# CAN_1.net
KiCad netlist of a schematic drawn in Altium Designer
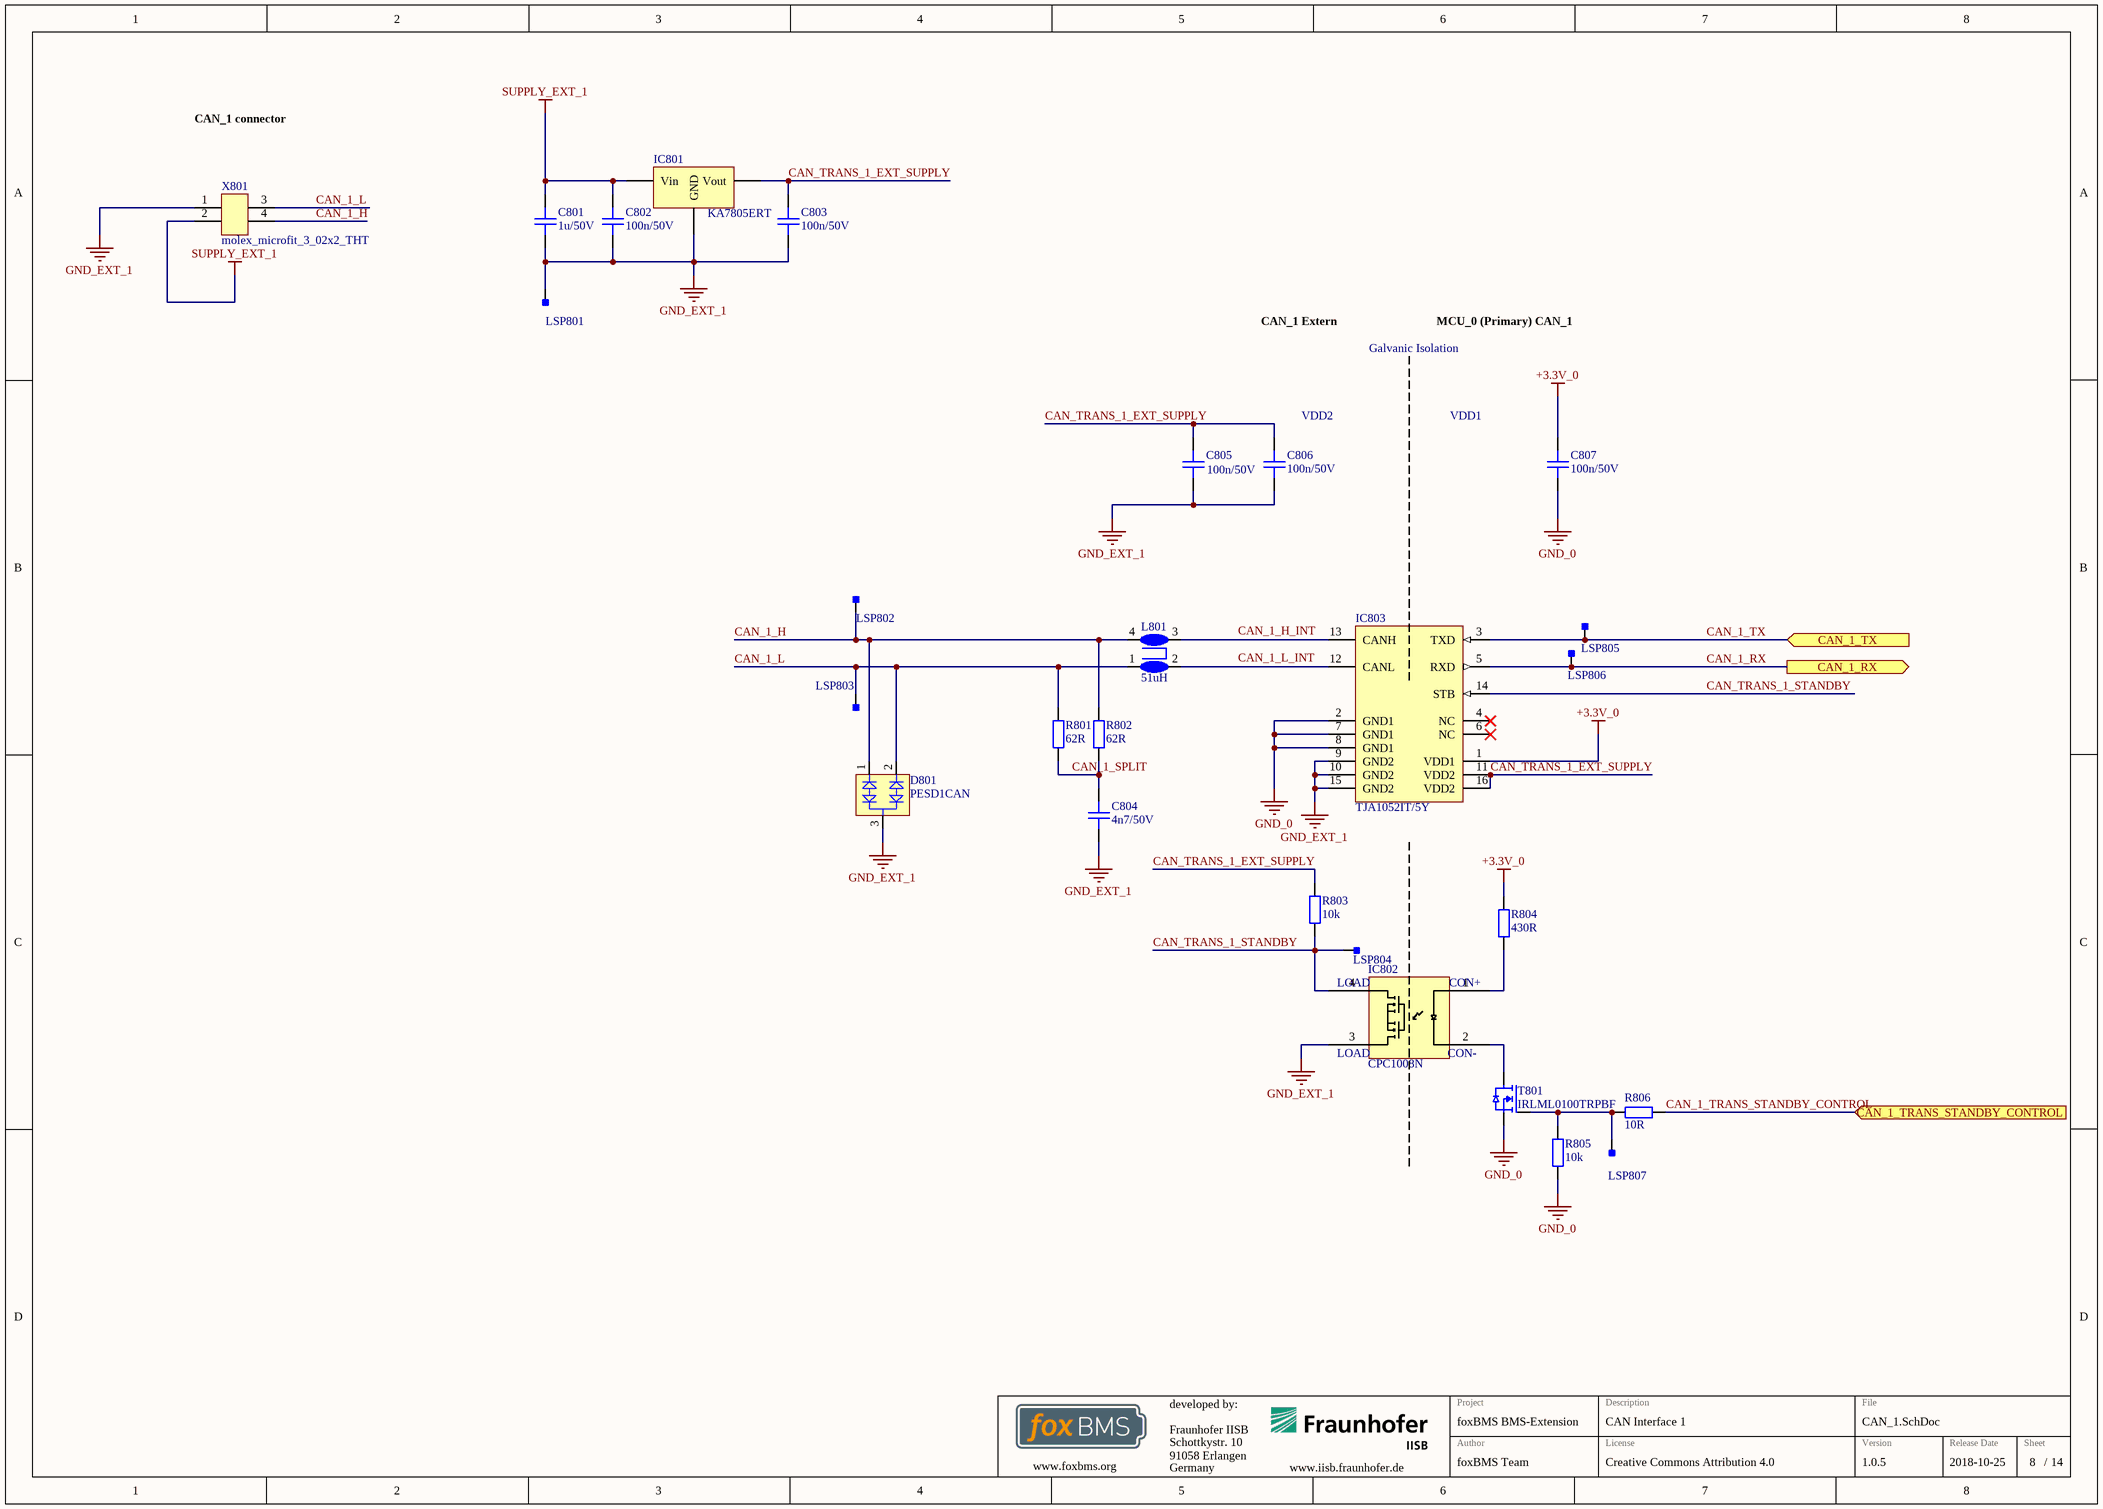
[diagram p0: CAN_1.SchDoc]

(export (version "E")
  (design (tool "Eeschema 10.0.6"))
  (components
    (comp (ref "C801")
      (value "1u/50V")
      (footprint "CAPC1608X08N")
      (description "MLCC")
      (fields (field (name "PART NUMBER") "gen_C_ceramic_1u_50V_X7R_0603") (field (name "TOLERANCE") "± 10%"))
      (libsource (lib "OE750") (part "C"))
    )
    (comp (ref "C802")
      (value "100n/50V")
      (footprint "CAPC1608X08N")
      (description "MLCC")
      (fields (field (name "PART NUMBER") "gen_C_ceramic_100n_50V_X7R_0603"))
      (libsource (lib "OE750") (part "C"))
    )
    (comp (ref "C803")
      (value "100n/50V")
      (footprint "CAPC1608X08N")
      (description "MLCC")
      (fields (field (name "PART NUMBER") "gen_C_ceramic_100n_50V_X7R_0603"))
      (libsource (lib "OE750") (part "C"))
    )
    (comp (ref "C804")
      (value "4n7/50V")
      (footprint "CAPC1608X08N")
      (description "MLCC")
      (fields (field (name "PART NUMBER") "gen_C_ceramic_4n7_50V_X7R_0603"))
      (libsource (lib "OE750") (part "C"))
    )
    (comp (ref "C805")
      (value "100n/50V")
      (footprint "CAPC1608X08N")
      (description "MLCC")
      (fields (field (name "PART NUMBER") "gen_C_ceramic_100n_50V_X7R_0603"))
      (libsource (lib "OE750") (part "C"))
    )
    (comp (ref "C806")
      (value "100n/50V")
      (footprint "CAPC1608X08N")
      (description "MLCC")
      (fields (field (name "PART NUMBER") "gen_C_ceramic_100n_50V_X7R_0603"))
      (libsource (lib "OE750") (part "C"))
    )
    (comp (ref "C807")
      (value "100n/50V")
      (footprint "CAPC1608X08N")
      (description "MLCC")
      (fields (field (name "PART NUMBER") "gen_C_ceramic_100n_50V_X7R_0603"))
      (libsource (lib "OE750") (part "C"))
    )
    (comp (ref "D801")
      (value "PESD1CAN")
      (footprint "NXP-SOT23-3_V")
      (description "CAN Bus ESD Protection Diode, 200 W, 24 V, -65 to 150 degC, 3-Pin SOT23, RoHS, Tape and Reel")
      (fields (field (name "MANUFACTURER") "NXP Semiconductors"))
      (libsource (lib "Altium Content Vault") (part "NXP-PESD1CAN-SOT23-3"))
    )
    (comp (ref "IC801")
      (value "KA7805ERT")
      (footprint "DPAK228P950X240-3N")
      (description "3-Terminal 1 A Positive Voltage Regulator")
      (fields (field (name "PART NUMBER") "KA7805ERTF") (field (name "MANUFACTURER") "Fairchild"))
      (libsource (lib "OE750") (part "KA7805ERT"))
    )
    (comp (ref "IC802")
      (value "CPC1008N")
      (footprint "SOP254P610X218-4N")
      (description "Single-Pole, Normally Open 4-Pin SOP OptoMOS Relay")
      (fields (field (name "MANUFACTURER") "CLARE"))
      (libsource (lib "OE750") (part "CPC1008N"))
    )
    (comp (ref "IC803")
      (value "TJA1052IT/5Y")
      (footprint "NXP-SOIC-16_L")
      (fields (field (name "MANUFACTURER") "NXPSemiconductors"))
      (libsource (lib "Altium Content Vault") (part "NXP-TJA1052IT-SOIC-16"))
    )
    (comp (ref "L801")
      (value "51uH")
      (footprint "B82789C0/S0")
      (description "Common Mode Choke")
      (fields (field (name "PART NUMBER") "B82789N") (field (name "MANUFACTURER") "EPCOS / TDK"))
      (libsource (lib "OE750") (part "L_CM"))
    )
    (comp (ref "LSP801")
      (value "Testpoint_Square")
      (footprint "Testpoint_S1")
      (description "Testpoint, square")
      (libsource (lib "OE750") (part "Testpoint_Square"))
    )
    (comp (ref "LSP802")
      (value "Testpoint_Square")
      (footprint "Testpoint_S1")
      (description "Testpoint, square")
      (libsource (lib "OE750") (part "Testpoint_Square"))
    )
    (comp (ref "LSP803")
      (value "Testpoint_Square")
      (footprint "Testpoint_S1")
      (description "Testpoint, square")
      (libsource (lib "OE750") (part "Testpoint_Square"))
    )
    (comp (ref "LSP804")
      (value "Testpoint_Square")
      (footprint "Testpoint_S1")
      (description "Testpoint, square")
      (libsource (lib "OE750") (part "Testpoint_Square"))
    )
    (comp (ref "LSP805")
      (value "Testpoint_Square")
      (footprint "Testpoint_S1")
      (description "Testpoint, square")
      (libsource (lib "OE750") (part "Testpoint_Square"))
    )
    (comp (ref "LSP806")
      (value "Testpoint_Square")
      (footprint "Testpoint_S1")
      (description "Testpoint, square")
      (libsource (lib "OE750") (part "Testpoint_Square"))
    )
    (comp (ref "LSP807")
      (value "Testpoint_Square")
      (footprint "Testpoint_S1")
      (description "Testpoint, square")
      (libsource (lib "OE750") (part "Testpoint_Square"))
    )
    (comp (ref "R801")
      (value "62R")
      (footprint "RESC1608X05N")
      (description "SMD Resistor 62R 0603")
      (fields (field (name "PART NUMBER") "gen_R_62R_0603") (field (name "TOLERANCE") "1%"))
      (libsource (lib "OE750") (part "R"))
    )
    (comp (ref "R802")
      (value "62R")
      (footprint "RESC1608X05N")
      (description "SMD Resistor 62R 0603")
      (fields (field (name "PART NUMBER") "gen_R_62R_0603") (field (name "TOLERANCE") "1%"))
      (libsource (lib "OE750") (part "R"))
    )
    (comp (ref "R803")
      (value "10k")
      (footprint "RESC1608X05N")
      (description "SMD Resistor 10k 0603")
      (fields (field (name "PART NUMBER") "gen_R_10k_0603") (field (name "TOLERANCE") "1%"))
      (libsource (lib "OE750") (part "R"))
    )
    (comp (ref "R804")
      (value "430R")
      (footprint "RESC1608X05N")
      (description "SMD Resistor 430R 0603")
      (fields (field (name "PART NUMBER") "gen_R_430R_0603") (field (name "TOLERANCE") "1%"))
      (libsource (lib "OE750") (part "R"))
    )
    (comp (ref "R805")
      (value "10k")
      (footprint "RESC1608X05N")
      (description "SMD Resistor 10k 0603")
      (fields (field (name "PART NUMBER") "gen_R_10k_0603") (field (name "TOLERANCE") "1%"))
      (libsource (lib "OE750") (part "R"))
    )
    (comp (ref "R806")
      (value "10R")
      (footprint "RESC1608X05N")
      (description "SMD Resistor 10R 0603")
      (fields (field (name "PART NUMBER") "gen_R_10R_0603") (field (name "TOLERANCE") "1%"))
      (libsource (lib "OE750") (part "R"))
    )
    (comp (ref "T801")
      (value "IRLML0100TRPBF")
      (footprint "SOT95P237X110-3N")
      (description "MOSFET-Transistor, n-Kanal, 1.6 A, 100 V, 0.178 ohm, 10 V, 2.5 V")
      (fields (field (name "MANUFACTURER") "Infineon"))
      (libsource (lib "OE750") (part "NMOS"))
    )
    (comp (ref "X801")
      (value "molex_microfit_3_02x2_THT")
      (footprint "MOLEX_MICROFIT_02x2_THT")
      (fields (field (name "MANUFACTURER") "Molex"))
      (libsource (lib "OE750") (part "X2x2"))
    )
  )
  (nets
    (net (code "1") (name "+3.3V_0") (class "Default")
      (node (ref "C807") (pin "2") (pinfunction "2_2") (pintype "passive"))
      (node (ref "IC803") (pin "1") (pinfunction "VDD1_1") (pintype "power_in"))
      (node (ref "R804") (pin "1") (pinfunction "1_1") (pintype "passive"))
    )
    (net (code "2") (name "/CAN_1_H") (class "Default")
      (node (ref "D801") (pin "1") (pinfunction "K1_1") (pintype "passive"))
      (node (ref "L801") (pin "4") (pinfunction "4_4") (pintype "passive"))
      (node (ref "LSP802") (pin "1") (pinfunction "1_1") (pintype "passive"))
      (node (ref "R802") (pin "2") (pinfunction "2_2") (pintype "passive"))
      (node (ref "X801") (pin "4") (pintype "passive"))
    )
    (net (code "4") (name "/CAN_1_L") (class "Default")
      (node (ref "D801") (pin "2") (pinfunction "K2_2") (pintype "passive"))
      (node (ref "L801") (pin "1") (pinfunction "1_1") (pintype "passive"))
      (node (ref "LSP803") (pin "1") (pinfunction "1_1") (pintype "passive"))
      (node (ref "R801") (pin "1") (pinfunction "1_1") (pintype "passive"))
      (node (ref "X801") (pin "3") (pintype "passive"))
    )
    (net (code "6") (name "/CAN_1_RX") (class "Default")
      (node (ref "IC803") (pin "5") (pinfunction "RXD_5") (pintype "output"))
      (node (ref "LSP806") (pin "1") (pinfunction "1_1") (pintype "passive"))
    )
    (net (code "7") (name "/CAN_1_SPLIT") (class "Default")
      (node (ref "C804") (pin "1") (pinfunction "1_1") (pintype "passive"))
      (node (ref "R801") (pin "2") (pinfunction "2_2") (pintype "passive"))
      (node (ref "R802") (pin "1") (pinfunction "1_1") (pintype "passive"))
    )
    (net (code "8") (name "/CAN_1_TRANS_STANDBY_CONTROL") (class "Default")
      (node (ref "R806") (pin "2") (pinfunction "2_2") (pintype "passive"))
    )
    (net (code "9") (name "/CAN_1_TX") (class "Default")
      (node (ref "IC803") (pin "3") (pinfunction "TXD_3") (pintype "input"))
      (node (ref "LSP805") (pin "1") (pinfunction "1_1") (pintype "passive"))
    )
    (net (code "10") (name "/CAN_TRANS_1_EXT_SUPPLY") (class "Default")
      (node (ref "C803") (pin "2") (pinfunction "2_2") (pintype "passive"))
      (node (ref "C805") (pin "2") (pinfunction "2_2") (pintype "passive"))
      (node (ref "C806") (pin "2") (pinfunction "2_2") (pintype "passive"))
      (node (ref "IC801") (pin "3") (pinfunction "Vout_3") (pintype "power_in"))
      (node (ref "IC803") (pin "11") (pinfunction "VDD2_11") (pintype "power_in"))
      (node (ref "IC803") (pin "16") (pinfunction "VDD2_16") (pintype "power_in"))
      (node (ref "R803") (pin "1") (pinfunction "1_1") (pintype "passive"))
    )
    (net (code "11") (name "/CAN_TRANS_1_STANDBY") (class "Default")
      (node (ref "IC802") (pin "4") (pintype "passive"))
      (node (ref "IC803") (pin "14") (pinfunction "STB_14") (pintype "input"))
      (node (ref "LSP804") (pin "1") (pinfunction "1_1") (pintype "passive"))
      (node (ref "R803") (pin "2") (pinfunction "2_2") (pintype "passive"))
    )
    (net (code "12") (name "GND_0") (class "Default")
      (node (ref "C807") (pin "1") (pinfunction "1_1") (pintype "passive"))
      (node (ref "IC803") (pin "2") (pinfunction "GND1_2") (pintype "power_in"))
      (node (ref "IC803") (pin "7") (pinfunction "GND1_7") (pintype "power_in"))
      (node (ref "IC803") (pin "8") (pinfunction "GND1_8") (pintype "power_in"))
      (node (ref "R805") (pin "2") (pinfunction "2_2") (pintype "passive"))
      (node (ref "T801") (pin "S") (pinfunction "S_S") (pintype "passive"))
    )
    (net (code "13") (name "GND_EXT_1") (class "Default")
      (node (ref "C801") (pin "1") (pinfunction "1_1") (pintype "passive"))
      (node (ref "C802") (pin "1") (pinfunction "1_1") (pintype "passive"))
      (node (ref "C803") (pin "1") (pinfunction "1_1") (pintype "passive"))
      (node (ref "C804") (pin "2") (pinfunction "2_2") (pintype "passive"))
      (node (ref "C805") (pin "1") (pinfunction "1_1") (pintype "passive"))
      (node (ref "C806") (pin "1") (pinfunction "1_1") (pintype "passive"))
      (node (ref "D801") (pin "3") (pinfunction "C_3") (pintype "passive"))
      (node (ref "IC801") (pin "2") (pinfunction "GND_2") (pintype "power_in"))
      (node (ref "IC802") (pin "3") (pintype "passive"))
      (node (ref "IC803") (pin "10") (pinfunction "GND2_10") (pintype "power_in"))
      (node (ref "IC803") (pin "15") (pinfunction "GND2_15") (pintype "power_in"))
      (node (ref "IC803") (pin "9") (pinfunction "GND2_9") (pintype "power_in"))
      (node (ref "LSP801") (pin "1") (pinfunction "1_1") (pintype "passive"))
      (node (ref "X801") (pin "1") (pintype "passive"))
    )
    (net (code "14") (name "Net-(IC802-Pad1)") (class "Default")
      (node (ref "IC802") (pin "1") (pintype "passive"))
      (node (ref "R804") (pin "2") (pinfunction "2_2") (pintype "passive"))
    )
    (net (code "15") (name "Net-(IC802-Pad2)") (class "Default")
      (node (ref "IC802") (pin "2") (pintype "power_in"))
      (node (ref "T801") (pin "D") (pinfunction "D_D") (pintype "passive"))
    )
    (net (code "16") (name "Net-(IC803-CANH)") (class "Default")
      (node (ref "IC803") (pin "13") (pinfunction "CANH_13") (pintype "passive"))
      (node (ref "L801") (pin "3") (pinfunction "3_3") (pintype "passive"))
    )
    (net (code "17") (name "Net-(IC803-CANL)") (class "Default")
      (node (ref "IC803") (pin "12") (pinfunction "CANL_12") (pintype "passive"))
      (node (ref "L801") (pin "2") (pinfunction "2_2") (pintype "passive"))
    )
    (net (code "18") (name "Net-(LSP807-Pad1)") (class "Default")
      (node (ref "LSP807") (pin "1") (pinfunction "1_1") (pintype "passive"))
      (node (ref "R805") (pin "1") (pinfunction "1_1") (pintype "passive"))
      (node (ref "R806") (pin "1") (pinfunction "1_1") (pintype "passive"))
      (node (ref "T801") (pin "G") (pinfunction "G_G") (pintype "passive"))
    )
    (net (code "19") (name "SUPPLY_EXT_1") (class "Default")
      (node (ref "C801") (pin "2") (pinfunction "2_2") (pintype "passive"))
      (node (ref "C802") (pin "2") (pinfunction "2_2") (pintype "passive"))
      (node (ref "IC801") (pin "1") (pinfunction "Vin_1") (pintype "power_in"))
      (node (ref "X801") (pin "2") (pintype "passive"))
    )
    (net (code "20") (name "unconnected-(IC803-NC-Pad4)") (class "Default")
      (node (ref "IC803") (pin "4") (pinfunction "NC_4") (pintype "passive+no_connect"))
    )
    (net (code "21") (name "unconnected-(IC803-NC-Pad6)") (class "Default")
      (node (ref "IC803") (pin "6") (pinfunction "NC_6") (pintype "passive+no_connect"))
    )
  )
)
